# terrarium_shield.net
KiCad netlist of a schematic drawn in EAGLE
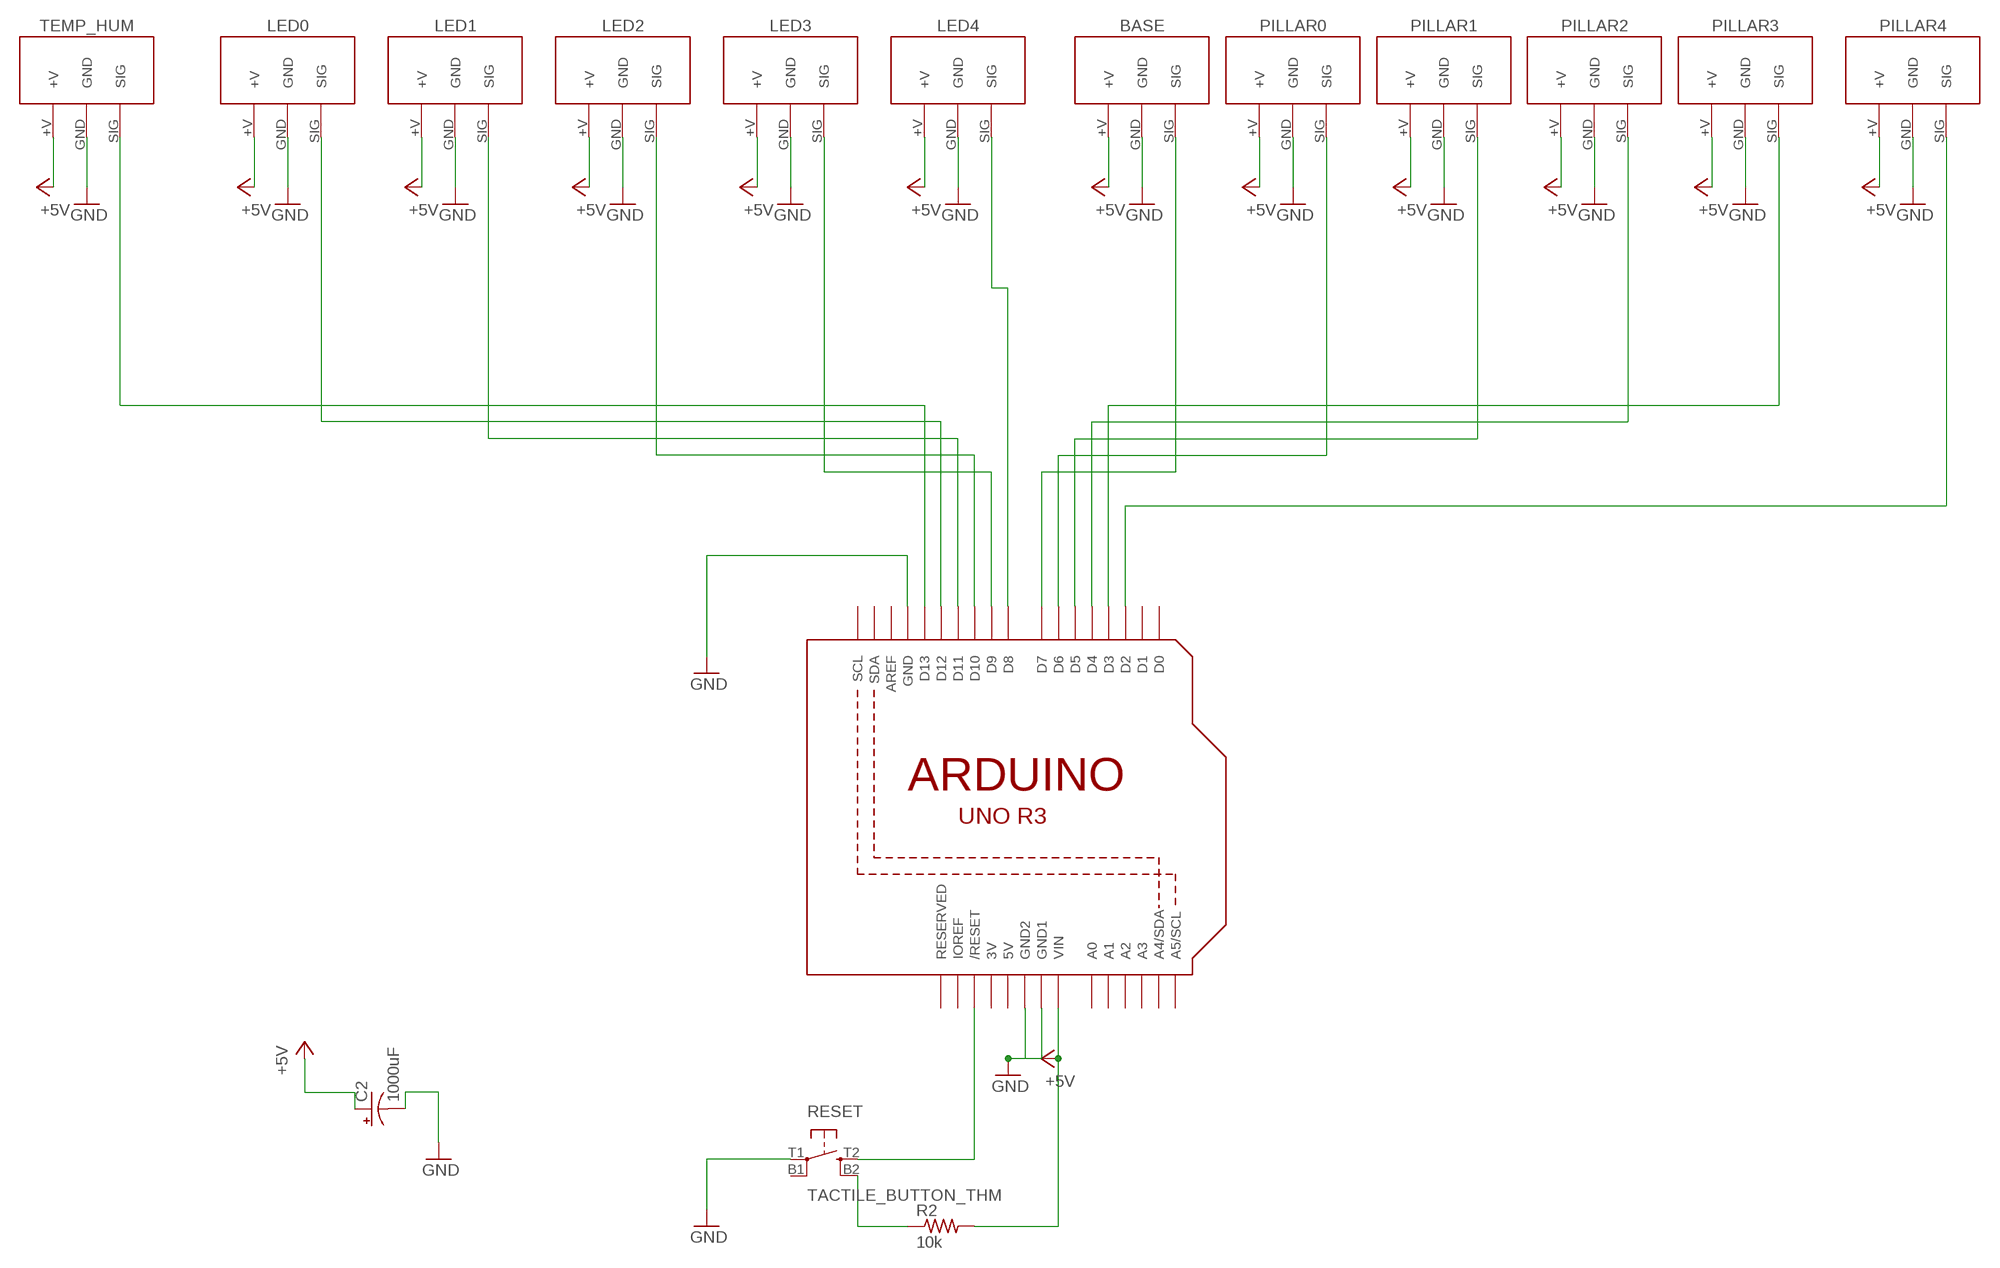
[diagram p0: schematic, sheet 1]

(export (version "E")
  (design (tool "Eeschema 10.0.6"))
  (components
    (comp (ref "BASE")
      (value "MOLEX_3PIN_VERT_THM")
      (footprint "eagle-import:MOLEX_3PIN_VERT_THM")
      (libsource (lib "eagle-import") (part "MOLEX_3PIN_VERT_THM"))
    )
    (comp (ref "C2")
      (value "1000uF")
      (footprint "eagle-import:CPOL-RADIAL-1000UF-25V")
      (libsource (lib "eagle-import") (part "CAP_POLPTH4"))
    )
    (comp (ref "LED0")
      (value "MOLEX_3PIN_VERT_THM")
      (footprint "eagle-import:MOLEX_3PIN_VERT_THM")
      (libsource (lib "eagle-import") (part "MOLEX_3PIN_VERT_THM"))
    )
    (comp (ref "LED1")
      (value "MOLEX_3PIN_VERT_THM")
      (footprint "eagle-import:MOLEX_3PIN_VERT_THM")
      (libsource (lib "eagle-import") (part "MOLEX_3PIN_VERT_THM"))
    )
    (comp (ref "LED2")
      (value "MOLEX_3PIN_VERT_THM")
      (footprint "eagle-import:MOLEX_3PIN_VERT_THM")
      (libsource (lib "eagle-import") (part "MOLEX_3PIN_VERT_THM"))
    )
    (comp (ref "LED3")
      (value "MOLEX_3PIN_VERT_THM")
      (footprint "eagle-import:MOLEX_3PIN_VERT_THM")
      (libsource (lib "eagle-import") (part "MOLEX_3PIN_VERT_THM"))
    )
    (comp (ref "LED4")
      (value "MOLEX_3PIN_VERT_THM")
      (footprint "eagle-import:MOLEX_3PIN_VERT_THM")
      (libsource (lib "eagle-import") (part "MOLEX_3PIN_VERT_THM"))
    )
    (comp (ref "PILLAR0")
      (value "MOLEX_3PIN_VERT_THM")
      (footprint "eagle-import:MOLEX_3PIN_VERT_THM")
      (libsource (lib "eagle-import") (part "MOLEX_3PIN_VERT_THM"))
    )
    (comp (ref "PILLAR1")
      (value "MOLEX_3PIN_VERT_THM")
      (footprint "eagle-import:MOLEX_3PIN_VERT_THM")
      (libsource (lib "eagle-import") (part "MOLEX_3PIN_VERT_THM"))
    )
    (comp (ref "PILLAR2")
      (value "MOLEX_3PIN_VERT_THM")
      (footprint "eagle-import:MOLEX_3PIN_VERT_THM")
      (libsource (lib "eagle-import") (part "MOLEX_3PIN_VERT_THM"))
    )
    (comp (ref "PILLAR3")
      (value "MOLEX_3PIN_VERT_THM")
      (footprint "eagle-import:MOLEX_3PIN_VERT_THM")
      (libsource (lib "eagle-import") (part "MOLEX_3PIN_VERT_THM"))
    )
    (comp (ref "PILLAR4")
      (value "MOLEX_3PIN_VERT_THM")
      (footprint "eagle-import:MOLEX_3PIN_VERT_THM")
      (libsource (lib "eagle-import") (part "MOLEX_3PIN_VERT_THM"))
    )
    (comp (ref "R2")
      (value "10k")
      (footprint "eagle-import:RESISTOR_THM")
      (libsource (lib "eagle-import") (part "RESISTOR_US_THM"))
    )
    (comp (ref "RESET")
      (value "TACTILE_BUTTON_THM")
      (footprint "eagle-import:TACTILE_BUTTON_THM")
      (libsource (lib "eagle-import") (part "TACTILE_BUTTON_THM"))
    )
    (comp (ref "TEMP_HUM")
      (value "MOLEX_3PIN_VERT_THM")
      (footprint "eagle-import:MOLEX_3PIN_VERT_THM")
      (libsource (lib "eagle-import") (part "MOLEX_3PIN_VERT_THM"))
    )
    (comp (ref "U$1")
      (value "ARDUINO_UNO_R3")
      (footprint "eagle-import:ARDUINO_UNO_R3")
      (libsource (lib "eagle-import") (part "ARDUINO_UNO_R3"))
    )
  )
  (nets
    (net (code "1") (name "+5V") (class "Default")
      (node (ref "BASE") (pin "+V") (pinfunction "+V_+V") (pintype "bidirectional"))
      (node (ref "C2") (pin "1") (pinfunction "+_1") (pintype "passive"))
      (node (ref "LED0") (pin "+V") (pinfunction "+V_+V") (pintype "bidirectional"))
      (node (ref "LED1") (pin "+V") (pinfunction "+V_+V") (pintype "bidirectional"))
      (node (ref "LED2") (pin "+V") (pinfunction "+V_+V") (pintype "bidirectional"))
      (node (ref "LED3") (pin "+V") (pinfunction "+V_+V") (pintype "bidirectional"))
      (node (ref "LED4") (pin "+V") (pinfunction "+V_+V") (pintype "bidirectional"))
      (node (ref "PILLAR0") (pin "+V") (pinfunction "+V_+V") (pintype "bidirectional"))
      (node (ref "PILLAR1") (pin "+V") (pinfunction "+V_+V") (pintype "bidirectional"))
      (node (ref "PILLAR2") (pin "+V") (pinfunction "+V_+V") (pintype "bidirectional"))
      (node (ref "PILLAR3") (pin "+V") (pinfunction "+V_+V") (pintype "bidirectional"))
      (node (ref "PILLAR4") (pin "+V") (pinfunction "+V_+V") (pintype "bidirectional"))
      (node (ref "R2") (pin "P$2") (pinfunction "2_P$2") (pintype "passive"))
      (node (ref "TEMP_HUM") (pin "+V") (pinfunction "+V_+V") (pintype "bidirectional"))
      (node (ref "U$1") (pin "VIN") (pinfunction "VIN_VIN") (pintype "power_in"))
    )
    (net (code "2") (name "/3V") (class "Default")
      (node (ref "U$1") (pin "3V") (pinfunction "3V_3V") (pintype "power_in"))
    )
    (net (code "3") (name "/5V") (class "Default")
      (node (ref "U$1") (pin "5V") (pinfunction "5V_5V") (pintype "power_in"))
    )
    (net (code "4") (name "GND") (class "Default")
      (node (ref "BASE") (pin "GND") (pinfunction "GND_GND") (pintype "bidirectional"))
      (node (ref "C2") (pin "2") (pinfunction "-_2") (pintype "passive"))
      (node (ref "LED0") (pin "GND") (pinfunction "GND_GND") (pintype "bidirectional"))
      (node (ref "LED1") (pin "GND") (pinfunction "GND_GND") (pintype "bidirectional"))
      (node (ref "LED2") (pin "GND") (pinfunction "GND_GND") (pintype "bidirectional"))
      (node (ref "LED3") (pin "GND") (pinfunction "GND_GND") (pintype "bidirectional"))
      (node (ref "LED4") (pin "GND") (pinfunction "GND_GND") (pintype "bidirectional"))
      (node (ref "PILLAR0") (pin "GND") (pinfunction "GND_GND") (pintype "bidirectional"))
      (node (ref "PILLAR1") (pin "GND") (pinfunction "GND_GND") (pintype "bidirectional"))
      (node (ref "PILLAR2") (pin "GND") (pinfunction "GND_GND") (pintype "bidirectional"))
      (node (ref "PILLAR3") (pin "GND") (pinfunction "GND_GND") (pintype "bidirectional"))
      (node (ref "PILLAR4") (pin "GND") (pinfunction "GND_GND") (pintype "bidirectional"))
      (node (ref "RESET") (pin "T1") (pinfunction "T1_T1") (pintype "passive"))
      (node (ref "TEMP_HUM") (pin "GND") (pinfunction "GND_GND") (pintype "bidirectional"))
      (node (ref "U$1") (pin "GND") (pinfunction "GND_GND") (pintype "power_in"))
      (node (ref "U$1") (pin "GND1") (pinfunction "GND1_GND1") (pintype "power_in"))
      (node (ref "U$1") (pin "GND2") (pinfunction "GND2_GND2") (pintype "power_in"))
    )
    (net (code "5") (name "Net-(BASE-PadSIG)") (class "Default")
      (node (ref "BASE") (pin "SIG") (pinfunction "SIG_SIG") (pintype "bidirectional"))
      (node (ref "U$1") (pin "D7") (pinfunction "D7_D7") (pintype "bidirectional"))
    )
    (net (code "6") (name "Net-(LED0-PadSIG)") (class "Default")
      (node (ref "LED0") (pin "SIG") (pinfunction "SIG_SIG") (pintype "bidirectional"))
      (node (ref "U$1") (pin "D12") (pinfunction "D12_D12") (pintype "bidirectional"))
    )
    (net (code "7") (name "Net-(LED1-PadSIG)") (class "Default")
      (node (ref "LED1") (pin "SIG") (pinfunction "SIG_SIG") (pintype "bidirectional"))
      (node (ref "U$1") (pin "D11") (pinfunction "D11_D11") (pintype "bidirectional"))
    )
    (net (code "8") (name "Net-(LED2-PadSIG)") (class "Default")
      (node (ref "LED2") (pin "SIG") (pinfunction "SIG_SIG") (pintype "bidirectional"))
      (node (ref "U$1") (pin "D10") (pinfunction "D10_D10") (pintype "bidirectional"))
    )
    (net (code "9") (name "Net-(LED3-PadSIG)") (class "Default")
      (node (ref "LED3") (pin "SIG") (pinfunction "SIG_SIG") (pintype "bidirectional"))
      (node (ref "U$1") (pin "D9") (pinfunction "D9_D9") (pintype "bidirectional"))
    )
    (net (code "10") (name "Net-(LED4-PadSIG)") (class "Default")
      (node (ref "LED4") (pin "SIG") (pinfunction "SIG_SIG") (pintype "bidirectional"))
      (node (ref "U$1") (pin "D8") (pinfunction "D8_D8") (pintype "bidirectional"))
    )
    (net (code "11") (name "Net-(PILLAR0-PadSIG)") (class "Default")
      (node (ref "PILLAR0") (pin "SIG") (pinfunction "SIG_SIG") (pintype "bidirectional"))
      (node (ref "U$1") (pin "D6") (pinfunction "D6_D6") (pintype "bidirectional"))
    )
    (net (code "12") (name "Net-(PILLAR1-PadSIG)") (class "Default")
      (node (ref "PILLAR1") (pin "SIG") (pinfunction "SIG_SIG") (pintype "bidirectional"))
      (node (ref "U$1") (pin "D5") (pinfunction "D5_D5") (pintype "bidirectional"))
    )
    (net (code "13") (name "Net-(PILLAR2-PadSIG)") (class "Default")
      (node (ref "PILLAR2") (pin "SIG") (pinfunction "SIG_SIG") (pintype "bidirectional"))
      (node (ref "U$1") (pin "D4") (pinfunction "D4_D4") (pintype "bidirectional"))
    )
    (net (code "14") (name "Net-(PILLAR3-PadSIG)") (class "Default")
      (node (ref "PILLAR3") (pin "SIG") (pinfunction "SIG_SIG") (pintype "bidirectional"))
      (node (ref "U$1") (pin "D3") (pinfunction "D3_D3") (pintype "bidirectional"))
    )
    (net (code "15") (name "Net-(PILLAR4-PadSIG)") (class "Default")
      (node (ref "PILLAR4") (pin "SIG") (pinfunction "SIG_SIG") (pintype "bidirectional"))
      (node (ref "U$1") (pin "D2") (pinfunction "D2_D2") (pintype "bidirectional"))
    )
    (net (code "16") (name "Net-(R2-1)") (class "Default")
      (node (ref "R2") (pin "P$1") (pinfunction "1_P$1") (pintype "passive"))
      (node (ref "RESET") (pin "B2") (pinfunction "B2_B2") (pintype "passive"))
    )
    (net (code "17") (name "Net-(TEMP_HUM-PadSIG)") (class "Default")
      (node (ref "TEMP_HUM") (pin "SIG") (pinfunction "SIG_SIG") (pintype "bidirectional"))
      (node (ref "U$1") (pin "D13") (pinfunction "D13_D13") (pintype "bidirectional"))
    )
    (net (code "18") (name "Net-(U$1-{slash}RESET)") (class "Default")
      (node (ref "RESET") (pin "T2") (pinfunction "T2_T2") (pintype "passive"))
      (node (ref "U$1") (pin "RESET") (pinfunction "/RESET_RESET") (pintype "bidirectional"))
    )
    (net (code "19") (name "unconnected-(RESET-PadB1)") (class "Default")
      (node (ref "RESET") (pin "B1") (pinfunction "B1_B1") (pintype "passive"))
    )
    (net (code "20") (name "unconnected-(U$1-A4{slash}SDA-PadA4)") (class "Default")
      (node (ref "U$1") (pin "A4") (pinfunction "A4/SDA_A4") (pintype "bidirectional"))
    )
    (net (code "21") (name "unconnected-(U$1-A5{slash}SCL-PadA5)") (class "Default")
      (node (ref "U$1") (pin "A5") (pinfunction "A5/SCL_A5") (pintype "bidirectional"))
    )
    (net (code "22") (name "unconnected-(U$1-PadA0)") (class "Default")
      (node (ref "U$1") (pin "A0") (pinfunction "A0_A0") (pintype "bidirectional"))
    )
    (net (code "23") (name "unconnected-(U$1-PadA1)") (class "Default")
      (node (ref "U$1") (pin "A1") (pinfunction "A1_A1") (pintype "bidirectional"))
    )
    (net (code "24") (name "unconnected-(U$1-PadA2)") (class "Default")
      (node (ref "U$1") (pin "A2") (pinfunction "A2_A2") (pintype "bidirectional"))
    )
    (net (code "25") (name "unconnected-(U$1-PadA3)") (class "Default")
      (node (ref "U$1") (pin "A3") (pinfunction "A3_A3") (pintype "bidirectional"))
    )
    (net (code "26") (name "unconnected-(U$1-PadAREF)") (class "Default")
      (node (ref "U$1") (pin "AREF") (pinfunction "AREF_AREF") (pintype "bidirectional"))
    )
    (net (code "27") (name "unconnected-(U$1-PadD0)") (class "Default")
      (node (ref "U$1") (pin "D0") (pinfunction "D0_D0") (pintype "bidirectional"))
    )
    (net (code "28") (name "unconnected-(U$1-PadD1)") (class "Default")
      (node (ref "U$1") (pin "D1") (pinfunction "D1_D1") (pintype "bidirectional"))
    )
    (net (code "29") (name "unconnected-(U$1-PadIOREF)") (class "Default")
      (node (ref "U$1") (pin "IOREF") (pinfunction "IOREF_IOREF") (pintype "output"))
    )
    (net (code "30") (name "unconnected-(U$1-PadRESERVED)") (class "Default")
      (node (ref "U$1") (pin "RESERVED") (pinfunction "RESERVED_RESERVED") (pintype "no_connect"))
    )
    (net (code "31") (name "unconnected-(U$1-PadSCL)") (class "Default")
      (node (ref "U$1") (pin "SCL") (pinfunction "SCL_SCL") (pintype "bidirectional"))
    )
    (net (code "32") (name "unconnected-(U$1-PadSDA)") (class "Default")
      (node (ref "U$1") (pin "SDA") (pinfunction "SDA_SDA") (pintype "bidirectional"))
    )
  )
)
